# TIDA-00641_SCH.net
KiCad netlist of a schematic drawn in Altium Designer
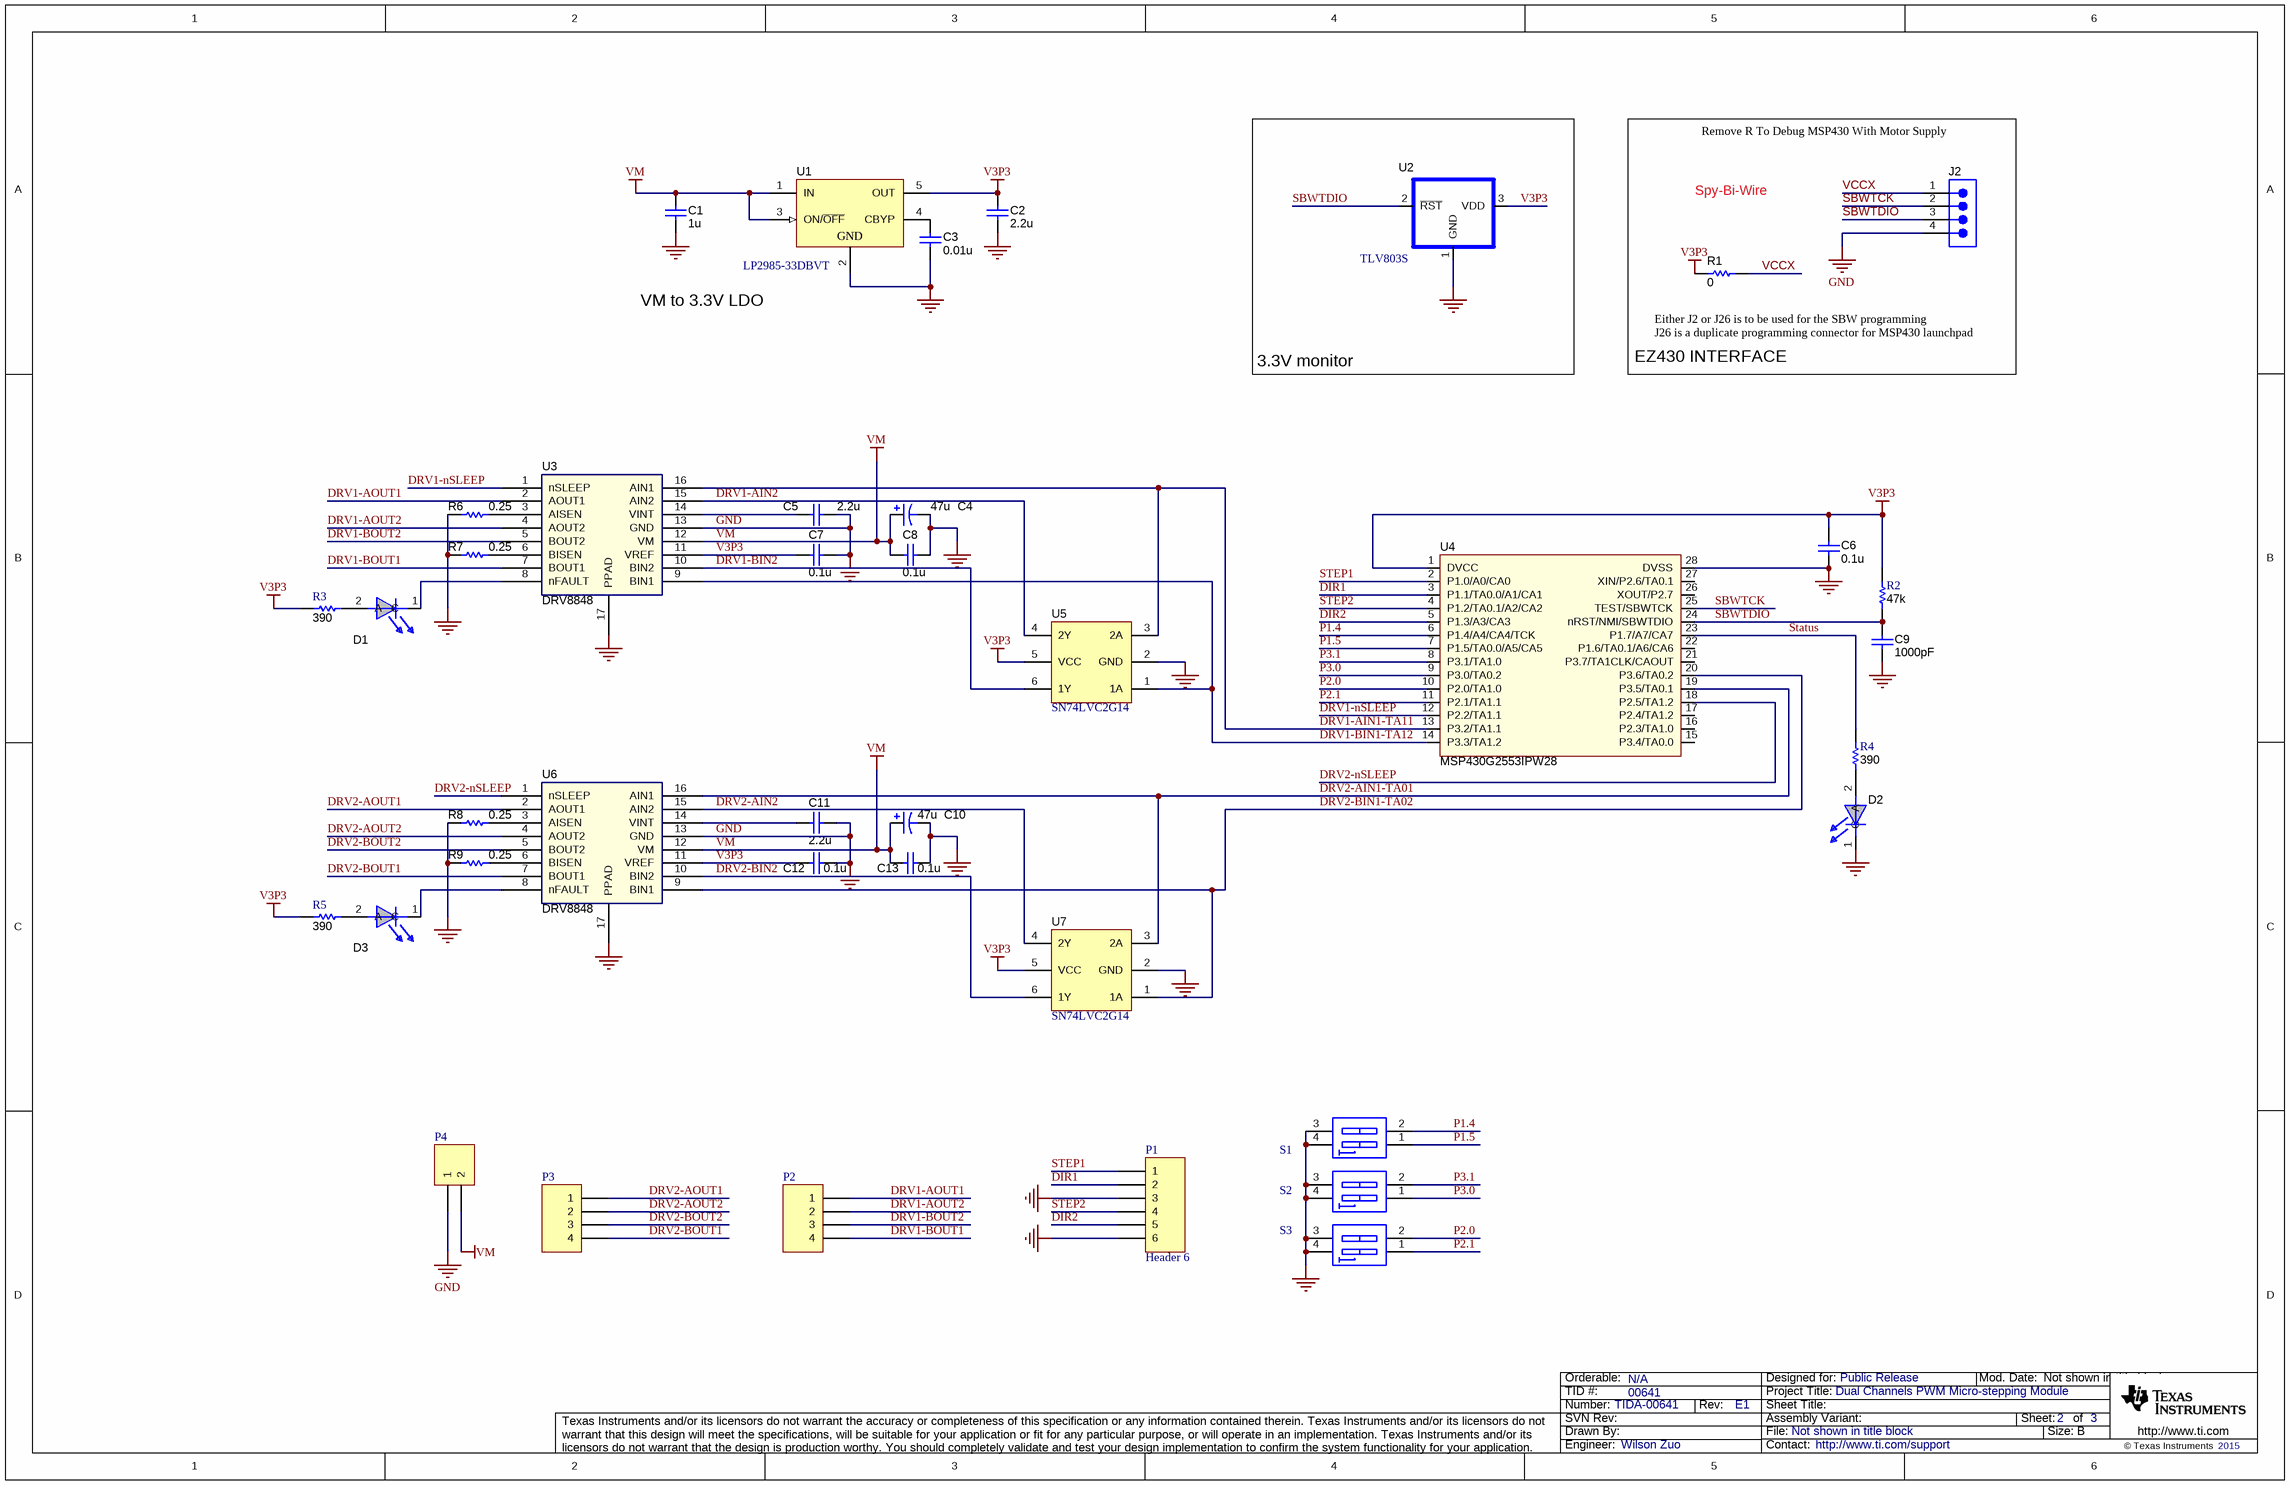
[diagram p0: TIDA-00641_SCH.SchDoc]

(export (version "E")
  (design (tool "Eeschema 10.0.6"))
  (components
    (comp (ref "C1")
      (value "C0603C105K4PACTU")
      (footprint "0603L")
      (description "CAP, CERM, 1uF, 16V, +/-10%, X5R, 0603")
      (fields
        (field (name "MANUFACTURER") "Kemet")
        (field (name "VALUEDISPLAYED") "1u")
        (field (name "PUBLISHER") "Texas Instruments")
      )
      (libsource (lib "Capacitor_Ceramic") (part "C0603C105K4PACTU"))
    )
    (comp (ref "C2")
      (value "C0603C225K8PACTU")
      (footprint "0603L")
      (description "CAP, CERM, 2.2uF, 10V, +/-10%, X5R, 0603")
      (fields
        (field (name "VALUEDISPLAYED") "2.2u")
        (field (name "MANUFACTURER") "Kemet")
        (field (name "PUBLISHER") "Texas Instruments")
      )
      (libsource (lib "Capacitor_Ceramic") (part "C0603C225K8PACTU"))
    )
    (comp (ref "C3")
      (value "C0603C103J5RACTU")
      (footprint "0603L")
      (description "CAP, CERM, 0.01uF, 50V, +/-5%, X7R, 0603")
      (fields
        (field (name "MANUFACTURER") "Kemet")
        (field (name "VALUEDISPLAYED") "0.01u")
        (field (name "PUBLISHER") "Texas Instruments")
      )
      (libsource (lib "Capacitor_Ceramic") (part "C0603C103J5RACTU"))
    )
    (comp (ref "C4")
      (value "EEE-FK1E470P")
      (footprint "SM_RADIAL_D")
      (description "CAP, AL, 47uF, 25V, +/-20%, 0.36 ohm, SMD")
      (fields
        (field (name "VALUEDISPLAYED") "47u")
        (field (name "MANUFACTURER") "Panasonic")
        (field (name "PUBLISHER") "Texas Instruments")
      )
      (libsource (lib "Capacitor_Aluminum") (part "EEE-FK1E470P"))
    )
    (comp (ref "C5")
      (value "C0603C225M8PACTU")
      (footprint "0603L")
      (description "CAP, CERM, 2.2uF, 10V, +/-20%, X5R, 0603")
      (fields
        (field (name "VALUEDISPLAYED") "2.2u")
        (field (name "MANUFACTURER") "Kemet")
        (field (name "PUBLISHER") "Texas Instruments")
      )
      (libsource (lib "Capacitor_Ceramic") (part "C0603C225M8PACTU"))
    )
    (comp (ref "C6")
      (value "C0603C104K4RACTU")
      (footprint "0603L")
      (description "CAP, CERM, 0.1uF, 16V, +/-10%, X7R, 0603")
      (fields
        (field (name "VALUEDISPLAYED") "0.1u")
        (field (name "MANUFACTURER") "Kemet")
        (field (name "PUBLISHER") "Texas Instruments")
      )
      (libsource (lib "Capacitor_Ceramic") (part "C0603C104K4RACTU"))
    )
    (comp (ref "C7")
      (value "06033C104KAT2A")
      (footprint "0603L")
      (description "CAP, CERM, 0.1uF, 25V, +/-10%, X7R, 0603")
      (fields
        (field (name "VALUEDISPLAYED") "0.1u")
        (field (name "MANUFACTURER") "AVX")
        (field (name "PUBLISHER") "Texas Instruments")
      )
      (libsource (lib "Capacitor_Ceramic") (part "06033C104KAT2A"))
    )
    (comp (ref "C8")
      (value "06033C104KAT2A")
      (footprint "0603L")
      (description "CAP, CERM, 0.1uF, 25V, +/-10%, X7R, 0603")
      (fields
        (field (name "VALUEDISPLAYED") "0.1u")
        (field (name "MANUFACTURER") "AVX")
        (field (name "PUBLISHER") "Texas Instruments")
      )
      (libsource (lib "Capacitor_Ceramic") (part "06033C104KAT2A"))
    )
    (comp (ref "C9")
      (value "C0603C102K5RACTU")
      (footprint "0603L")
      (description "CAP, CERM, 1000pF, 50V, +/-10%, X7R, 0603")
      (fields
        (field (name "VALUEDISPLAYED") "1000pF")
        (field (name "MANUFACTURER") "Kemet")
        (field (name "PUBLISHER") "Texas Instruments")
      )
      (libsource (lib "Capacitor_Ceramic") (part "C0603C102K5RACTU"))
    )
    (comp (ref "C10")
      (value "EEE-FK1E470P")
      (footprint "SM_RADIAL_D")
      (description "CAP, AL, 47uF, 25V, +/-20%, 0.36 ohm, SMD")
      (fields
        (field (name "VALUEDISPLAYED") "47u")
        (field (name "MANUFACTURER") "Panasonic")
        (field (name "PUBLISHER") "Texas Instruments")
      )
      (libsource (lib "Capacitor_Aluminum") (part "EEE-FK1E470P"))
    )
    (comp (ref "C11")
      (value "C0603C225K8PACTU")
      (footprint "0603L")
      (description "CAP, CERM, 2.2uF, 10V, +/-10%, X5R, 0603")
      (fields
        (field (name "VALUEDISPLAYED") "2.2u")
        (field (name "MANUFACTURER") "Kemet")
        (field (name "PUBLISHER") "Texas Instruments")
      )
      (libsource (lib "Capacitor_Ceramic") (part "C0603C225K8PACTU"))
    )
    (comp (ref "C12")
      (value "06033C104KAT2A")
      (footprint "0603L")
      (description "CAP, CERM, 0.1uF, 25V, +/-10%, X7R, 0603")
      (fields
        (field (name "VALUEDISPLAYED") "0.1u")
        (field (name "MANUFACTURER") "AVX")
        (field (name "PUBLISHER") "Texas Instruments")
      )
      (libsource (lib "Capacitor_Ceramic") (part "06033C104KAT2A"))
    )
    (comp (ref "C13")
      (value "06033C104KAT2A")
      (footprint "0603L")
      (description "CAP, CERM, 0.1uF, 25V, +/-10%, X7R, 0603")
      (fields
        (field (name "VALUEDISPLAYED") "0.1u")
        (field (name "MANUFACTURER") "AVX")
        (field (name "PUBLISHER") "Texas Instruments")
      )
      (libsource (lib "Capacitor_Ceramic") (part "06033C104KAT2A"))
    )
    (comp (ref "D1")
      (value "LTST-C190KRKT")
      (footprint "LED603RED")
      (description "LED SUPER RED CLEAR 0603 SMD")
      (fields (field (name "MANUFACTURER") "Lite On"))
      (libsource (lib "PADSlegacy_Active") (part "D_LED_603_GRN"))
    )
    (comp (ref "D2")
      (value "LTST-C190GKT")
      (footprint "LED603GRN")
      (description "Diode, LED, Green, 2.1-V, 20-mA, 6-mcd")
      (fields (field (name "MANUFACTURER") "Lite On"))
      (libsource (lib "PADSlegacy_Active") (part "D_LED_603_GRN"))
    )
    (comp (ref "D3")
      (value "LTST-C190KRKT")
      (footprint "LED603RED")
      (description "LED SUPER RED CLEAR 0603 SMD")
      (fields (field (name "MANUFACTURER") "Lite On"))
      (libsource (lib "PADSlegacy_Active") (part "D_LED_603_GRN"))
    )
    (comp (ref "J2")
      (value "TSW-104-07-G-S")
      (footprint "HDR1X4")
      (description "Header, TH, 100mil, 4x1, Gold plated, 230 mil above insulator")
      (fields
        (field (name "MANUFACTURER") "Samtec, Inc.")
        (field (name "PUBLISHER") "Texas Instruments")
        (field (name "SYMBOLCREATOR") "a0412235")
      )
      (libsource (lib "Connectors") (part "TSW-104-07-G-S"))
    )
    (comp (ref "P1")
      (value "Header 6")
      (footprint "HDR1X6")
      (description "Header, 6-Pin")
      (fields (field (name "PUBLISHER") "Altium Limited"))
      (libsource (lib "Miscellaneous Connectors") (part "Header 6"))
    )
    (comp (ref "P2")
      (value "Header 4")
      (footprint "J4-3.81")
      (description "Header, 4-Pin")
      (fields (field (name "PUBLISHER") "Altium Limited"))
      (libsource (lib "Miscellaneous Connectors") (part "Header 4"))
    )
    (comp (ref "P3")
      (value "Header 4")
      (footprint "J4-3.81")
      (description "Header, 4-Pin")
      (fields (field (name "PUBLISHER") "Altium Limited"))
      (libsource (lib "Miscellaneous Connectors") (part "Header 4"))
    )
    (comp (ref "P4")
      (value "Header 2")
      (footprint "j2-3.81")
      (description "Header, 2-Pin")
      (fields (field (name "PUBLISHER") "Altium Limited"))
      (libsource (lib "Miscellaneous Connectors") (part "Header 2"))
    )
    (comp (ref "R1")
      (value "0")
      (footprint "0603L")
      (description "RES, 0 ohm, 5%, 0.1W, 0603")
      (fields
        (field (name "PARTNUMBER") "ERJ-3GEY0R00V")
        (field (name "MANUFACTURER") "Panasonic")
        (field (name "PUBLISHER") "Texas Instruments")
      )
      (libsource (lib "Resistor_0603") (part "ERJ-3GEY0R00V"))
    )
    (comp (ref "R2")
      (value "47k")
      (footprint "0603L")
      (description "RES, 47k ohm, 5%, 0.1W, 0603")
      (fields
        (field (name "PARTNUMBER") "CRCW060347K0JNEA")
        (field (name "MANUFACTURER") "Vishay-Dale")
        (field (name "PUBLISHER") "Texas Instruments")
      )
      (libsource (lib "Resistor_0603") (part "CRCW060347K0JNEA"))
    )
    (comp (ref "R3")
      (value "390")
      (footprint "0603L")
      (description "RES, 390 ohm, 1%, 0.1W, 0603")
      (fields
        (field (name "PARTNUMBER") "RC0603FR-07390RL")
        (field (name "MANUFACTURER") "Yageo America")
        (field (name "PUBLISHER") "Texas Instruments")
      )
      (libsource (lib "Resistor_0603") (part "RC0603FR-07390RL"))
    )
    (comp (ref "R4")
      (value "390")
      (footprint "0603L")
      (description "RES, 390 ohm, 1%, 0.1W, 0603")
      (fields
        (field (name "PARTNUMBER") "RC0603FR-07390RL")
        (field (name "MANUFACTURER") "Yageo America")
        (field (name "PUBLISHER") "Texas Instruments")
      )
      (libsource (lib "Resistor_0603") (part "RC0603FR-07390RL"))
    )
    (comp (ref "R5")
      (value "390")
      (footprint "0603L")
      (description "RES, 390 ohm, 1%, 0.1W, 0603")
      (fields
        (field (name "PARTNUMBER") "RC0603FR-07390RL")
        (field (name "MANUFACTURER") "Yageo America")
        (field (name "PUBLISHER") "Texas Instruments")
      )
      (libsource (lib "Resistor_0603") (part "RC0603FR-07390RL"))
    )
    (comp (ref "R6")
      (value "0.25")
      (footprint "2512M")
      (description "RES, 0.25 ohm, 1%, 2W, 2512")
      (fields
        (field (name "PARTNUMBER") "CSRN2512FKR250")
        (field (name "MANUFACTURER") "Stackpole Electronics Inc")
        (field (name "PUBLISHER") "Texas Instruments")
      )
      (libsource (lib "Resistor_OtherSMT") (part "CSRN2512FKR250"))
    )
    (comp (ref "R7")
      (value "0.25")
      (footprint "2512M")
      (description "RES, 0.25 ohm, 1%, 2W, 2512")
      (fields
        (field (name "PARTNUMBER") "CSRN2512FKR250")
        (field (name "MANUFACTURER") "Stackpole Electronics Inc")
        (field (name "PUBLISHER") "Texas Instruments")
      )
      (libsource (lib "Resistor_OtherSMT") (part "CSRN2512FKR250"))
    )
    (comp (ref "R8")
      (value "0.25")
      (footprint "2512M")
      (description "RES, 0.25 ohm, 1%, 2W, 2512")
      (fields
        (field (name "PARTNUMBER") "CSRN2512FKR250")
        (field (name "MANUFACTURER") "Stackpole Electronics Inc")
        (field (name "PUBLISHER") "Texas Instruments")
      )
      (libsource (lib "Resistor_OtherSMT") (part "CSRN2512FKR250"))
    )
    (comp (ref "R9")
      (value "0.25")
      (footprint "2512M")
      (description "RES, 0.25 ohm, 1%, 2W, 2512")
      (fields
        (field (name "PARTNUMBER") "CSRN2512FKR250")
        (field (name "MANUFACTURER") "Stackpole Electronics Inc")
        (field (name "PUBLISHER") "Texas Instruments")
      )
      (libsource (lib "Resistor_OtherSMT") (part "CSRN2512FKR250"))
    )
    (comp (ref "S1")
      (value "SW DIP-2")
      (footprint "DIP-4")
      (description "SWITCH TIN CONT 2 SEC 50V")
      (fields (field (name "PUBLISHER") "Altium Limited"))
      (libsource (lib "Miscellaneous Devices") (part "SW DIP-2"))
    )
    (comp (ref "S2")
      (value "SW DIP-2")
      (footprint "DIP-4")
      (description "SWITCH TIN CONT 2 SEC 50V")
      (fields (field (name "PUBLISHER") "Altium Limited"))
      (libsource (lib "Miscellaneous Devices") (part "SW DIP-2"))
    )
    (comp (ref "S3")
      (value "SW DIP-2")
      (footprint "DIP-4")
      (description "SWITCH TIN CONT 2 SEC 50V")
      (fields (field (name "PUBLISHER") "Altium Limited"))
      (libsource (lib "Miscellaneous Devices") (part "SW DIP-2"))
    )
    (comp (ref "U1")
      (value "LP2985-33DBVT")
      (footprint "MF05A_L")
      (description "Micropower 150 mA Low-Noise Ultra Low-Dropout Regulator, 5-pin SOT-23")
      (fields
        (field (name "PARTNUMBER") "LP2985IM5-3.3")
        (field (name "MANUFACTURER") "National Semiconductor")
        (field (name "PUBLISHER") "Altium Limited")
      )
      (libsource (lib "NSC LDO") (part "LP2985IM5-3.3"))
    )
    (comp (ref "U2")
      (value "TLV803S")
      (footprint "SOT-23")
      (description "IC VOLT SUPERVISR 2.93V SOT23-3")
      (fields (field (name "MANUFACTURER") "TI") (field (name "PARTNUMBER") "TLV803SDBZR"))
      (libsource (lib "PADSlegacy_PMP") (part "TLV803DBZ"))
    )
    (comp (ref "U3")
      (value "DRV8848")
      (footprint "PW0016S")
      (description "IC MOTOR DRIVER PAR 16HTSSOP")
      (fields
        (field (name "MANUFACTURER") "Used in BOM report")
        (field (name "MANUFACTURER_1") "Texas Instruments")
        (field (name "SYMBOLCREATOR") "Use a-id")
      )
      (libsource (lib "MDBU_Library_Elements") (part "DRV8848PWP"))
    )
    (comp (ref "U4")
      (value "MSP430G2553IPW28")
      (footprint "PW0028A_N")
      (description "IC MCU 16BIT 16KB FLASH 28TSSOP")
      (fields (field (name "MANUFACTURER") "TI"))
      (libsource (lib "DRV8865_EVM_E1") (part "MSP430G2553IPW28"))
    )
    (comp (ref "U5")
      (value "SN74LVC2G14")
      (footprint "DBV0006A_N")
      (description "Dual Schmitt-Trigger Inverter")
      (fields (field (name "MANUFACTURER") "Texas Instruments") (field (name "PARTNUMBER") "SN74LVC2G14DBVR"))
      (libsource (lib "TIDA-DRV8848PWM") (part "SN74LVC2G14"))
    )
    (comp (ref "U6")
      (value "DRV8848")
      (footprint "PW0016S")
      (description "IC MOTOR DRIVER PAR 16HTSSOP")
      (fields
        (field (name "MANUFACTURER") "Used in BOM report")
        (field (name "MANUFACTURER_1") "Texas Instruments")
        (field (name "SYMBOLCREATOR") "Use a-id")
      )
      (libsource (lib "MDBU_Library_Elements") (part "DRV8848PWP"))
    )
    (comp (ref "U7")
      (value "SN74LVC2G14")
      (footprint "DBV0006A_N")
      (description "Dual Schmitt-Trigger Inverter")
      (fields (field (name "MANUFACTURER") "Texas Instruments") (field (name "PARTNUMBER") "SN74LVC2G14DBVR"))
      (libsource (lib "TIDA-DRV8848PWM") (part "SN74LVC2G14"))
    )
  )
  (nets
    (net (code "1") (name "/DIR1") (class "Default")
      (node (ref "P1") (pin "2") (pinfunction "2_2") (pintype "passive"))
      (node (ref "U4") (pin "3") (pinfunction "P1.1/TA0.0/A1/CA1_3") (pintype "passive"))
    )
    (net (code "2") (name "/DIR2") (class "Default")
      (node (ref "P1") (pin "5") (pinfunction "5_5") (pintype "passive"))
      (node (ref "U4") (pin "5") (pinfunction "P1.3/A3/CA3_5") (pintype "passive"))
    )
    (net (code "3") (name "/DRV1-AIN1-TA11") (class "Default")
      (node (ref "U3") (pin "16") (pinfunction "AIN1_16") (pintype "passive"))
      (node (ref "U4") (pin "13") (pinfunction "P3.2/TA1.1_13") (pintype "passive"))
      (node (ref "U5") (pin "3") (pinfunction "2A_3") (pintype "passive"))
    )
    (net (code "4") (name "/DRV1-AIN2") (class "Default")
      (node (ref "U3") (pin "15") (pinfunction "AIN2_15") (pintype "passive"))
      (node (ref "U5") (pin "4") (pinfunction "2Y_4") (pintype "passive"))
    )
    (net (code "5") (name "/DRV1-AOUT1") (class "Default")
      (node (ref "P2") (pin "1") (pinfunction "1_1") (pintype "passive"))
      (node (ref "U3") (pin "2") (pinfunction "AOUT1_2") (pintype "passive"))
    )
    (net (code "6") (name "/DRV1-AOUT2") (class "Default")
      (node (ref "P2") (pin "2") (pinfunction "2_2") (pintype "passive"))
      (node (ref "U3") (pin "4") (pinfunction "AOUT2_4") (pintype "passive"))
    )
    (net (code "7") (name "/DRV1-BIN1-TA12") (class "Default")
      (node (ref "U3") (pin "9") (pinfunction "BIN1_9") (pintype "passive"))
      (node (ref "U4") (pin "14") (pinfunction "P3.3/TA1.2_14") (pintype "passive"))
      (node (ref "U5") (pin "1") (pinfunction "1A_1") (pintype "passive"))
    )
    (net (code "8") (name "/DRV1-BIN2") (class "Default")
      (node (ref "U3") (pin "10") (pinfunction "BIN2_10") (pintype "passive"))
      (node (ref "U5") (pin "6") (pinfunction "1Y_6") (pintype "passive"))
    )
    (net (code "9") (name "/DRV1-BOUT1") (class "Default")
      (node (ref "P2") (pin "4") (pinfunction "4_4") (pintype "passive"))
      (node (ref "U3") (pin "7") (pinfunction "BOUT1_7") (pintype "passive"))
    )
    (net (code "10") (name "/DRV1-BOUT2") (class "Default")
      (node (ref "P2") (pin "3") (pinfunction "3_3") (pintype "passive"))
      (node (ref "U3") (pin "5") (pinfunction "BOUT2_5") (pintype "passive"))
    )
    (net (code "11") (name "/DRV1-nSLEEP") (class "Default")
      (node (ref "U3") (pin "1") (pinfunction "nSLEEP_1") (pintype "passive"))
      (node (ref "U4") (pin "12") (pinfunction "P2.2/TA1.1_12") (pintype "passive"))
    )
    (net (code "12") (name "/DRV2-AIN1-TA01") (class "Default")
      (node (ref "U4") (pin "19") (pinfunction "P3.5/TA0.1_19") (pintype "passive"))
      (node (ref "U6") (pin "16") (pinfunction "AIN1_16") (pintype "passive"))
      (node (ref "U7") (pin "3") (pinfunction "2A_3") (pintype "passive"))
    )
    (net (code "13") (name "/DRV2-AIN2") (class "Default")
      (node (ref "U6") (pin "15") (pinfunction "AIN2_15") (pintype "passive"))
      (node (ref "U7") (pin "4") (pinfunction "2Y_4") (pintype "passive"))
    )
    (net (code "14") (name "/DRV2-AOUT1") (class "Default")
      (node (ref "P3") (pin "1") (pinfunction "1_1") (pintype "passive"))
      (node (ref "U6") (pin "2") (pinfunction "AOUT1_2") (pintype "passive"))
    )
    (net (code "15") (name "/DRV2-AOUT2") (class "Default")
      (node (ref "P3") (pin "2") (pinfunction "2_2") (pintype "passive"))
      (node (ref "U6") (pin "4") (pinfunction "AOUT2_4") (pintype "passive"))
    )
    (net (code "16") (name "/DRV2-BIN1-TA02") (class "Default")
      (node (ref "U4") (pin "20") (pinfunction "P3.6/TA0.2_20") (pintype "passive"))
      (node (ref "U6") (pin "9") (pinfunction "BIN1_9") (pintype "passive"))
      (node (ref "U7") (pin "1") (pinfunction "1A_1") (pintype "passive"))
    )
    (net (code "17") (name "/DRV2-BIN2") (class "Default")
      (node (ref "U6") (pin "10") (pinfunction "BIN2_10") (pintype "passive"))
      (node (ref "U7") (pin "6") (pinfunction "1Y_6") (pintype "passive"))
    )
    (net (code "18") (name "/DRV2-BOUT1") (class "Default")
      (node (ref "P3") (pin "4") (pinfunction "4_4") (pintype "passive"))
      (node (ref "U6") (pin "7") (pinfunction "BOUT1_7") (pintype "passive"))
    )
    (net (code "19") (name "/DRV2-BOUT2") (class "Default")
      (node (ref "P3") (pin "3") (pinfunction "3_3") (pintype "passive"))
      (node (ref "U6") (pin "5") (pinfunction "BOUT2_5") (pintype "passive"))
    )
    (net (code "20") (name "/DRV2-nSLEEP") (class "Default")
      (node (ref "U4") (pin "18") (pinfunction "P2.5/TA1.2_18") (pintype "passive"))
      (node (ref "U6") (pin "1") (pinfunction "nSLEEP_1") (pintype "passive"))
    )
    (net (code "21") (name "/P1.4") (class "Default")
      (node (ref "S1") (pin "2") (pinfunction "A2_2") (pintype "passive"))
      (node (ref "U4") (pin "6") (pinfunction "P1.4/A4/CA4/TCK_6") (pintype "passive"))
    )
    (net (code "22") (name "/P1.5") (class "Default")
      (node (ref "S1") (pin "1") (pinfunction "A1_1") (pintype "passive"))
      (node (ref "U4") (pin "7") (pinfunction "P1.5/TA0.0/A5/CA5_7") (pintype "passive"))
    )
    (net (code "23") (name "/P2.0") (class "Default")
      (node (ref "S3") (pin "2") (pinfunction "A2_2") (pintype "passive"))
      (node (ref "U4") (pin "10") (pinfunction "P2.0/TA1.0_10") (pintype "passive"))
    )
    (net (code "24") (name "/P2.1") (class "Default")
      (node (ref "S3") (pin "1") (pinfunction "A1_1") (pintype "passive"))
      (node (ref "U4") (pin "11") (pinfunction "P2.1/TA1.1_11") (pintype "passive"))
    )
    (net (code "25") (name "/P3.0") (class "Default")
      (node (ref "S2") (pin "1") (pinfunction "A1_1") (pintype "passive"))
      (node (ref "U4") (pin "9") (pinfunction "P3.0/TA0.2_9") (pintype "passive"))
    )
    (net (code "26") (name "/P3.1") (class "Default")
      (node (ref "S2") (pin "2") (pinfunction "A2_2") (pintype "passive"))
      (node (ref "U4") (pin "8") (pinfunction "P3.1/TA1.0_8") (pintype "passive"))
    )
    (net (code "27") (name "/SBWTCK") (class "Default")
      (node (ref "J2") (pin "2") (pinfunction "2_2") (pintype "passive"))
      (node (ref "U4") (pin "25") (pinfunction "TEST/SBWTCK_25") (pintype "passive"))
    )
    (net (code "28") (name "/SBWTDIO") (class "Default")
      (node (ref "C9") (pin "2") (pinfunction "2_2") (pintype "passive"))
      (node (ref "J2") (pin "3") (pinfunction "3_3") (pintype "passive"))
      (node (ref "R2") (pin "2") (pinfunction "2_2") (pintype "passive"))
      (node (ref "U2") (pin "2") (pinfunction "RST_2") (pintype "passive"))
      (node (ref "U4") (pin "24") (pinfunction "nRST/NMI/SBWTDIO_24") (pintype "passive"))
    )
    (net (code "29") (name "/STEP1") (class "Default")
      (node (ref "P1") (pin "1") (pinfunction "1_1") (pintype "passive"))
      (node (ref "U4") (pin "2") (pinfunction "P1.0/A0/CA0_2") (pintype "passive"))
    )
    (net (code "30") (name "/STEP2") (class "Default")
      (node (ref "P1") (pin "4") (pinfunction "4_4") (pintype "passive"))
      (node (ref "U4") (pin "4") (pinfunction "P1.2/TA0.1/A2/CA2_4") (pintype "passive"))
    )
    (net (code "31") (name "/Status") (class "Default")
      (node (ref "R4") (pin "2") (pinfunction "2_2") (pintype "passive"))
      (node (ref "U4") (pin "23") (pinfunction "P1.7/A7/CA7_23") (pintype "passive"))
    )
    (net (code "32") (name "/VCCX") (class "Default")
      (node (ref "J2") (pin "1") (pinfunction "1_1") (pintype "passive"))
      (node (ref "R1") (pin "2") (pinfunction "2_2") (pintype "passive"))
    )
    (net (code "33") (name "GND") (class "Default")
      (node (ref "C1") (pin "2") (pinfunction "2_2") (pintype "passive"))
      (node (ref "C10") (pin "2") (pinfunction "-_2") (pintype "passive"))
      (node (ref "C11") (pin "2") (pinfunction "2_2") (pintype "passive"))
      (node (ref "C12") (pin "1") (pinfunction "1_1") (pintype "passive"))
      (node (ref "C13") (pin "1") (pinfunction "1_1") (pintype "passive"))
      (node (ref "C2") (pin "1") (pinfunction "1_1") (pintype "passive"))
      (node (ref "C3") (pin "2") (pinfunction "2_2") (pintype "passive"))
      (node (ref "C4") (pin "2") (pinfunction "-_2") (pintype "passive"))
      (node (ref "C5") (pin "2") (pinfunction "2_2") (pintype "passive"))
      (node (ref "C6") (pin "1") (pinfunction "1_1") (pintype "passive"))
      (node (ref "C7") (pin "1") (pinfunction "1_1") (pintype "passive"))
      (node (ref "C8") (pin "1") (pinfunction "1_1") (pintype "passive"))
      (node (ref "C9") (pin "1") (pinfunction "1_1") (pintype "passive"))
      (node (ref "D2") (pin "1") (pinfunction "C_1") (pintype "passive"))
      (node (ref "J2") (pin "4") (pinfunction "4_4") (pintype "passive"))
      (node (ref "P1") (pin "3") (pinfunction "3_3") (pintype "passive"))
      (node (ref "P1") (pin "6") (pinfunction "6_6") (pintype "passive"))
      (node (ref "P4") (pin "1") (pinfunction "1_1") (pintype "passive"))
      (node (ref "R6") (pin "1") (pinfunction "1_1") (pintype "passive"))
      (node (ref "R7") (pin "1") (pinfunction "1_1") (pintype "passive"))
      (node (ref "R8") (pin "1") (pinfunction "1_1") (pintype "passive"))
      (node (ref "R9") (pin "1") (pinfunction "1_1") (pintype "passive"))
      (node (ref "S1") (pin "3") (pinfunction "B2_3") (pintype "passive"))
      (node (ref "S1") (pin "4") (pinfunction "B1_4") (pintype "passive"))
      (node (ref "S2") (pin "3") (pinfunction "B2_3") (pintype "passive"))
      (node (ref "S2") (pin "4") (pinfunction "B1_4") (pintype "passive"))
      (node (ref "S3") (pin "3") (pinfunction "B2_3") (pintype "passive"))
      (node (ref "S3") (pin "4") (pinfunction "B1_4") (pintype "passive"))
      (node (ref "U1") (pin "2") (pinfunction "GND_2") (pintype "power_in"))
      (node (ref "U2") (pin "1") (pinfunction "GND_1") (pintype "passive"))
      (node (ref "U3") (pin "13") (pinfunction "GND_13") (pintype "passive"))
      (node (ref "U3") (pin "17") (pinfunction "PPAD_17") (pintype "passive"))
      (node (ref "U4") (pin "28") (pinfunction "DVSS_28") (pintype "passive"))
      (node (ref "U5") (pin "2") (pinfunction "GND_2") (pintype "power_in"))
      (node (ref "U6") (pin "13") (pinfunction "GND_13") (pintype "passive"))
      (node (ref "U6") (pin "17") (pinfunction "PPAD_17") (pintype "passive"))
      (node (ref "U7") (pin "2") (pinfunction "GND_2") (pintype "power_in"))
    )
    (net (code "34") (name "Net-(D1-A)") (class "Default")
      (node (ref "D1") (pin "2") (pinfunction "A_2") (pintype "passive"))
      (node (ref "R3") (pin "1") (pinfunction "1_1") (pintype "passive"))
    )
    (net (code "35") (name "Net-(D1-C)") (class "Default")
      (node (ref "D1") (pin "1") (pinfunction "C_1") (pintype "passive"))
      (node (ref "U3") (pin "8") (pinfunction "nFAULT_8") (pintype "passive"))
    )
    (net (code "36") (name "Net-(D2-A)") (class "Default")
      (node (ref "D2") (pin "2") (pinfunction "A_2") (pintype "passive"))
      (node (ref "R4") (pin "1") (pinfunction "1_1") (pintype "passive"))
    )
    (net (code "37") (name "Net-(D3-A)") (class "Default")
      (node (ref "D3") (pin "2") (pinfunction "A_2") (pintype "passive"))
      (node (ref "R5") (pin "1") (pinfunction "1_1") (pintype "passive"))
    )
    (net (code "38") (name "Net-(D3-C)") (class "Default")
      (node (ref "D3") (pin "1") (pinfunction "C_1") (pintype "passive"))
      (node (ref "U6") (pin "8") (pinfunction "nFAULT_8") (pintype "passive"))
    )
    (net (code "39") (name "Net-(U1-CBYP)") (class "Default")
      (node (ref "C3") (pin "1") (pinfunction "1_1") (pintype "passive"))
      (node (ref "U1") (pin "4") (pinfunction "CBYP_4") (pintype "passive"))
    )
    (net (code "40") (name "Net-(U3-AISEN)") (class "Default")
      (node (ref "R6") (pin "2") (pinfunction "2_2") (pintype "passive"))
      (node (ref "U3") (pin "3") (pinfunction "AISEN_3") (pintype "passive"))
    )
    (net (code "41") (name "Net-(U3-BISEN)") (class "Default")
      (node (ref "R7") (pin "2") (pinfunction "2_2") (pintype "passive"))
      (node (ref "U3") (pin "6") (pinfunction "BISEN_6") (pintype "passive"))
    )
    (net (code "42") (name "Net-(U3-VINT)") (class "Default")
      (node (ref "C5") (pin "1") (pinfunction "1_1") (pintype "passive"))
      (node (ref "U3") (pin "14") (pinfunction "VINT_14") (pintype "passive"))
    )
    (net (code "43") (name "Net-(U6-AISEN)") (class "Default")
      (node (ref "R8") (pin "2") (pinfunction "2_2") (pintype "passive"))
      (node (ref "U6") (pin "3") (pinfunction "AISEN_3") (pintype "passive"))
    )
    (net (code "44") (name "Net-(U6-BISEN)") (class "Default")
      (node (ref "R9") (pin "2") (pinfunction "2_2") (pintype "passive"))
      (node (ref "U6") (pin "6") (pinfunction "BISEN_6") (pintype "passive"))
    )
    (net (code "45") (name "Net-(U6-VINT)") (class "Default")
      (node (ref "C11") (pin "1") (pinfunction "1_1") (pintype "passive"))
      (node (ref "U6") (pin "14") (pinfunction "VINT_14") (pintype "passive"))
    )
    (net (code "46") (name "V3P3") (class "Default")
      (node (ref "C12") (pin "2") (pinfunction "2_2") (pintype "passive"))
      (node (ref "C2") (pin "2") (pinfunction "2_2") (pintype "passive"))
      (node (ref "C6") (pin "2") (pinfunction "2_2") (pintype "passive"))
      (node (ref "C7") (pin "2") (pinfunction "2_2") (pintype "passive"))
      (node (ref "R1") (pin "1") (pinfunction "1_1") (pintype "passive"))
      (node (ref "R2") (pin "1") (pinfunction "1_1") (pintype "passive"))
      (node (ref "R3") (pin "2") (pinfunction "2_2") (pintype "passive"))
      (node (ref "R5") (pin "2") (pinfunction "2_2") (pintype "passive"))
      (node (ref "U1") (pin "5") (pinfunction "OUT_5") (pintype "power_in"))
      (node (ref "U2") (pin "3") (pinfunction "VDD_3") (pintype "passive"))
      (node (ref "U3") (pin "11") (pinfunction "VREF_11") (pintype "passive"))
      (node (ref "U4") (pin "1") (pinfunction "DVCC_1") (pintype "passive"))
      (node (ref "U5") (pin "5") (pinfunction "VCC_5") (pintype "power_in"))
      (node (ref "U6") (pin "11") (pinfunction "VREF_11") (pintype "passive"))
      (node (ref "U7") (pin "5") (pinfunction "VCC_5") (pintype "power_in"))
    )
    (net (code "47") (name "VM") (class "Default")
      (node (ref "C1") (pin "1") (pinfunction "1_1") (pintype "passive"))
      (node (ref "C10") (pin "1") (pinfunction "+_1") (pintype "passive"))
      (node (ref "C13") (pin "2") (pinfunction "2_2") (pintype "passive"))
      (node (ref "C4") (pin "1") (pinfunction "+_1") (pintype "passive"))
      (node (ref "C8") (pin "2") (pinfunction "2_2") (pintype "passive"))
      (node (ref "P4") (pin "2") (pinfunction "2_2") (pintype "passive"))
      (node (ref "U1") (pin "1") (pinfunction "IN_1") (pintype "power_in"))
      (node (ref "U1") (pin "3") (pinfunction "ON/~{OFF}_3") (pintype "input"))
      (node (ref "U3") (pin "12") (pinfunction "VM_12") (pintype "passive"))
      (node (ref "U6") (pin "12") (pinfunction "VM_12") (pintype "passive"))
    )
    (net (code "48") (name "unconnected-(U4-P1.6{slash}TA0.1{slash}A6{slash}CA6-Pad22)") (class "Default")
      (node (ref "U4") (pin "22") (pinfunction "P1.6/TA0.1/A6/CA6_22") (pintype "passive"))
    )
    (net (code "49") (name "unconnected-(U4-P2.3{slash}TA1.0-Pad16)") (class "Default")
      (node (ref "U4") (pin "16") (pinfunction "P2.3/TA1.0_16") (pintype "passive"))
    )
    (net (code "50") (name "unconnected-(U4-P2.4{slash}TA1.2-Pad17)") (class "Default")
      (node (ref "U4") (pin "17") (pinfunction "P2.4/TA1.2_17") (pintype "passive"))
    )
    (net (code "51") (name "unconnected-(U4-P3.4{slash}TA0.0-Pad15)") (class "Default")
      (node (ref "U4") (pin "15") (pinfunction "P3.4/TA0.0_15") (pintype "passive"))
    )
    (net (code "52") (name "unconnected-(U4-P3.7{slash}TA1CLK{slash}CAOUT-Pad21)") (class "Default")
      (node (ref "U4") (pin "21") (pinfunction "P3.7/TA1CLK/CAOUT_21") (pintype "passive"))
    )
    (net (code "53") (name "unconnected-(U4-XIN{slash}P2.6{slash}TA0.1-Pad27)") (class "Default")
      (node (ref "U4") (pin "27") (pinfunction "XIN/P2.6/TA0.1_27") (pintype "passive"))
    )
    (net (code "54") (name "unconnected-(U4-XOUT{slash}P2.7-Pad26)") (class "Default")
      (node (ref "U4") (pin "26") (pinfunction "XOUT/P2.7_26") (pintype "passive"))
    )
  )
)
